# 06_MicroSD_Card.net
KiCad netlist of a schematic drawn in Altium Designer
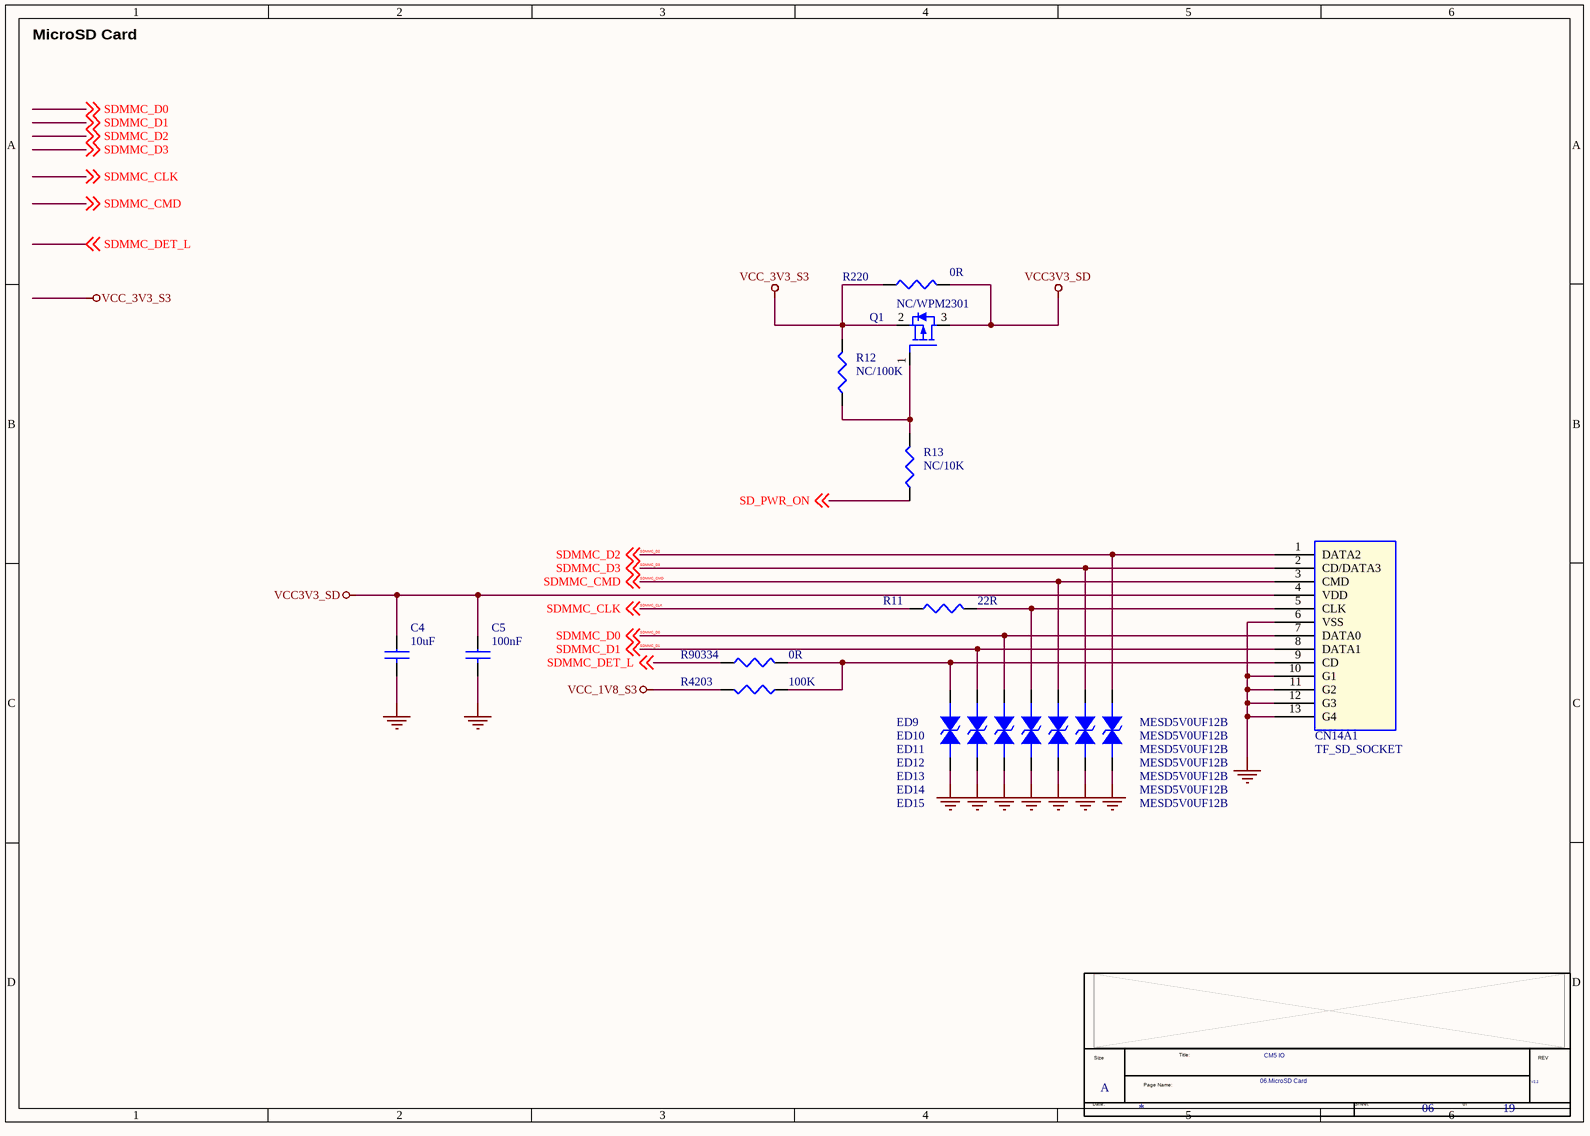
[diagram p0: 06_MicroSD_Card.SchDoc]

(export (version "E")
  (design (tool "Eeschema 10.0.6"))
  (components
    (comp (ref "*")
      (value "radxa_1010")
      (fields
        (field (name "DOC") "06.MicroSD Card")
        (field (name "REVCODE") "V2.2")
        (field (name "TITLE") "CM5 IO")
        (field (name "PAGE SIZE") "A")
        (field (name "PAGE NUMBER") "06")
        (field (name "PAGE COUNT") "19")
      )
      (libsource (lib "*") (part "radxa_1010"))
    )
    (comp (ref "C4")
      (value "10uF")
      (footprint "C0603")
      (description "cap,10.00uF,+/-10%,10V,X5R,C0603")
      (fields
        (field (name "VOLTAGE") "10V")
        (field (name "MANUFACTURER") "TDK")
        (field (name "CREATED BY") "JJJ")
      )
      (libsource (lib "*") (part "CAP NP_0"))
    )
    (comp (ref "C5")
      (value "100nF")
      (footprint "C0402")
      (description "cap,100.00nF,+/-10%,10V,X5R,C0402")
      (fields
        (field (name "VOLTAGE") "10V")
        (field (name "MANUFACTURER") "TDK")
        (field (name "CREATED BY") "JJJ")
      )
      (libsource (lib "*") (part "CAP NP_0"))
    )
    (comp (ref "CN14A1")
      (value "TF_SD_SOCKET")
      (footprint "TF-CKT01-009D")
      (libsource (lib "*") (part "SD_SOCKET_0"))
    )
    (comp (ref "ED9")
      (value "MESD5V0UF12B")
      (footprint "E0402N")
      (description "ESD")
      (libsource (lib "*") (part "DIODE BI-DIR TRIG"))
    )
    (comp (ref "ED10")
      (value "MESD5V0UF12B")
      (footprint "E0402N")
      (description "ESD")
      (libsource (lib "*") (part "DIODE BI-DIR TRIG"))
    )
    (comp (ref "ED11")
      (value "MESD5V0UF12B")
      (footprint "E0402N")
      (description "ESD")
      (libsource (lib "*") (part "DIODE BI-DIR TRIG"))
    )
    (comp (ref "ED12")
      (value "MESD5V0UF12B")
      (footprint "E0402N")
      (description "ESD")
      (libsource (lib "*") (part "DIODE BI-DIR TRIG"))
    )
    (comp (ref "ED13")
      (value "MESD5V0UF12B")
      (footprint "E0402N")
      (description "ESD")
      (libsource (lib "*") (part "DIODE BI-DIR TRIG"))
    )
    (comp (ref "ED14")
      (value "MESD5V0UF12B")
      (footprint "E0402N")
      (description "ESD")
      (libsource (lib "*") (part "DIODE BI-DIR TRIG"))
    )
    (comp (ref "ED15")
      (value "MESD5V0UF12B")
      (footprint "E0402N")
      (description "ESD")
      (libsource (lib "*") (part "DIODE BI-DIR TRIG"))
    )
    (comp (ref "Q1")
      (value "NC/WPM2301")
      (footprint "SOT23")
      (description "PMOS,WPM3407-3/TR,SOT_23,Id=4.4A,Vds=30V")
      (fields (field (name "MANUFACTURER") "WillSemi(韦尔半导体)") (field (name "CREATED BY") "JJJ"))
      (libsource (lib "*") (part "MOSFET P"))
    )
    (comp (ref "R11") (value "22R") (footprint "R0402") (libsource (lib "*") (part "RESISTOR_1_Dup2")))
    (comp (ref "R12")
      (value "NC/100K")
      (footprint "R0402")
      (description "通用厚膜电阻,100K,+/-5%,R0402,1/16W.")
      (fields
        (field (name "TOLERANCE") "5%")
        (field (name "MANUFACTURER") "YAGEO")
        (field (name "CREATED BY") "YTL")
      )
      (libsource (lib "*") (part "RESISTOR_0_Dup3"))
    )
    (comp (ref "R13")
      (value "NC/10K")
      (footprint "R0402")
      (description "通用厚膜电阻,10K,+/-5%,R0402,1/16W.")
      (fields
        (field (name "TOLERANCE") "5%")
        (field (name "MANUFACTURER") "YAGEO")
        (field (name "CREATED BY") "YTL")
      )
      (libsource (lib "*") (part "RESISTOR_0_Dup3"))
    )
    (comp (ref "R220")
      (value "0R")
      (footprint "R0402")
      (description "通用厚膜电阻,0R,+/-5%,R0402,1/16W.")
      (fields
        (field (name "TOLERANCE") "5%")
        (field (name "MANUFACTURER") "YAGEO")
        (field (name "CREATED BY") "YTL")
      )
      (libsource (lib "*") (part "RESISTOR_0_Dup3"))
    )
    (comp (ref "R4203")
      (value "100K")
      (footprint "R0402")
      (description "通用厚膜电阻,100K,+/-5%,R0402,1/16W.")
      (fields
        (field (name "TOLERANCE") "5%")
        (field (name "MANUFACTURER") "YAGEO")
        (field (name "CREATED BY") "YTL")
      )
      (libsource (lib "*") (part "RESISTOR_1"))
    )
    (comp (ref "R90334")
      (value "0R")
      (footprint "R0402")
      (description "通用厚膜电阻,0R,+/-5%,R0402,1/16W.")
      (fields
        (field (name "TOLERANCE") "5%")
        (field (name "MANUFACTURER") "YAGEO")
        (field (name "CREATED BY") "YTL")
      )
      (libsource (lib "*") (part "RESISTOR_0_Dup2"))
    )
  )
  (nets
    (net (code "1") (name "GND") (class "Default")
      (node (ref "C4") (pin "2") (pinfunction "2_2") (pintype "passive"))
      (node (ref "C5") (pin "2") (pinfunction "2_2") (pintype "passive"))
      (node (ref "CN14A1") (pin "10") (pinfunction "G1_10") (pintype "passive"))
      (node (ref "CN14A1") (pin "11") (pinfunction "G2_11") (pintype "passive"))
      (node (ref "CN14A1") (pin "12") (pinfunction "G3_12") (pintype "passive"))
      (node (ref "CN14A1") (pin "13") (pinfunction "G4_13") (pintype "passive"))
      (node (ref "CN14A1") (pin "6") (pinfunction "VSS_6") (pintype "passive"))
      (node (ref "ED10") (pin "2") (pinfunction "2_2") (pintype "passive"))
      (node (ref "ED11") (pin "2") (pinfunction "2_2") (pintype "passive"))
      (node (ref "ED12") (pin "2") (pinfunction "2_2") (pintype "passive"))
      (node (ref "ED13") (pin "2") (pinfunction "2_2") (pintype "passive"))
      (node (ref "ED14") (pin "2") (pinfunction "2_2") (pintype "passive"))
      (node (ref "ED15") (pin "2") (pinfunction "2_2") (pintype "passive"))
      (node (ref "ED9") (pin "2") (pinfunction "2_2") (pintype "passive"))
    )
    (net (code "2") (name "Net-(CN14A1-CD)") (class "Default")
      (node (ref "CN14A1") (pin "9") (pinfunction "CD_9") (pintype "passive"))
      (node (ref "ED9") (pin "1") (pinfunction "1_1") (pintype "passive"))
      (node (ref "R4203") (pin "1") (pinfunction "1_1") (pintype "passive"))
      (node (ref "R90334") (pin "2") (pinfunction "2_2") (pintype "passive"))
    )
    (net (code "3") (name "Net-(CN14A1-CLK)") (class "Default")
      (node (ref "CN14A1") (pin "5") (pinfunction "CLK_5") (pintype "passive"))
      (node (ref "ED12") (pin "1") (pinfunction "1_1") (pintype "passive"))
      (node (ref "R11") (pin "2") (pinfunction "2_2") (pintype "passive"))
    )
    (net (code "4") (name "Net-(Q1-GATE)") (class "Default")
      (node (ref "Q1") (pin "1") (pinfunction "GATE_1") (pintype "passive"))
      (node (ref "R12") (pin "2") (pinfunction "2_2") (pintype "passive"))
      (node (ref "R13") (pin "1") (pinfunction "1_1") (pintype "passive"))
    )
    (net (code "5") (name "SDMMC_CLK") (class "Default")
      (node (ref "R11") (pin "1") (pinfunction "1_1") (pintype "passive"))
    )
    (net (code "6") (name "SDMMC_CMD") (class "Default")
      (node (ref "CN14A1") (pin "3") (pinfunction "CMD_3") (pintype "passive"))
      (node (ref "ED13") (pin "1") (pinfunction "1_1") (pintype "passive"))
    )
    (net (code "7") (name "SDMMC_D0") (class "Default")
      (node (ref "CN14A1") (pin "7") (pinfunction "DATA0_7") (pintype "passive"))
      (node (ref "ED11") (pin "1") (pinfunction "1_1") (pintype "passive"))
    )
    (net (code "8") (name "SDMMC_D1") (class "Default")
      (node (ref "CN14A1") (pin "8") (pinfunction "DATA1_8") (pintype "passive"))
      (node (ref "ED10") (pin "1") (pinfunction "1_1") (pintype "passive"))
    )
    (net (code "9") (name "SDMMC_D2") (class "Default")
      (node (ref "CN14A1") (pin "1") (pinfunction "DATA2_1") (pintype "passive"))
      (node (ref "ED15") (pin "1") (pinfunction "1_1") (pintype "passive"))
    )
    (net (code "10") (name "SDMMC_D3") (class "Default")
      (node (ref "CN14A1") (pin "2") (pinfunction "CD/DATA3_2") (pintype "passive"))
      (node (ref "ED14") (pin "1") (pinfunction "1_1") (pintype "passive"))
    )
    (net (code "11") (name "SDMMC_DET_L") (class "Default")
      (node (ref "R90334") (pin "1") (pinfunction "1_1") (pintype "passive"))
    )
    (net (code "12") (name "SD_PWR_ON") (class "Default")
      (node (ref "R13") (pin "2") (pinfunction "2_2") (pintype "passive"))
    )
    (net (code "13") (name "VCC3V3_SD") (class "Default")
      (node (ref "C4") (pin "1") (pinfunction "1_1") (pintype "passive"))
      (node (ref "C5") (pin "1") (pinfunction "1_1") (pintype "passive"))
      (node (ref "CN14A1") (pin "4") (pinfunction "VDD_4") (pintype "passive"))
      (node (ref "Q1") (pin "3") (pinfunction "DRAIN_3") (pintype "passive"))
      (node (ref "R220") (pin "2") (pinfunction "2_2") (pintype "passive"))
    )
    (net (code "14") (name "VCC_1V8_S3") (class "Default")
      (node (ref "R4203") (pin "2") (pinfunction "2_2") (pintype "passive"))
    )
    (net (code "15") (name "VCC_3V3_S3") (class "Default")
      (node (ref "Q1") (pin "2") (pinfunction "SOURCE_2") (pintype "passive"))
      (node (ref "R12") (pin "1") (pinfunction "1_1") (pintype "passive"))
      (node (ref "R220") (pin "1") (pinfunction "1_1") (pintype "passive"))
    )
  )
)
